# M3_Shield_Solar_V1_2.net
KiCad netlist of a schematic drawn in EAGLE
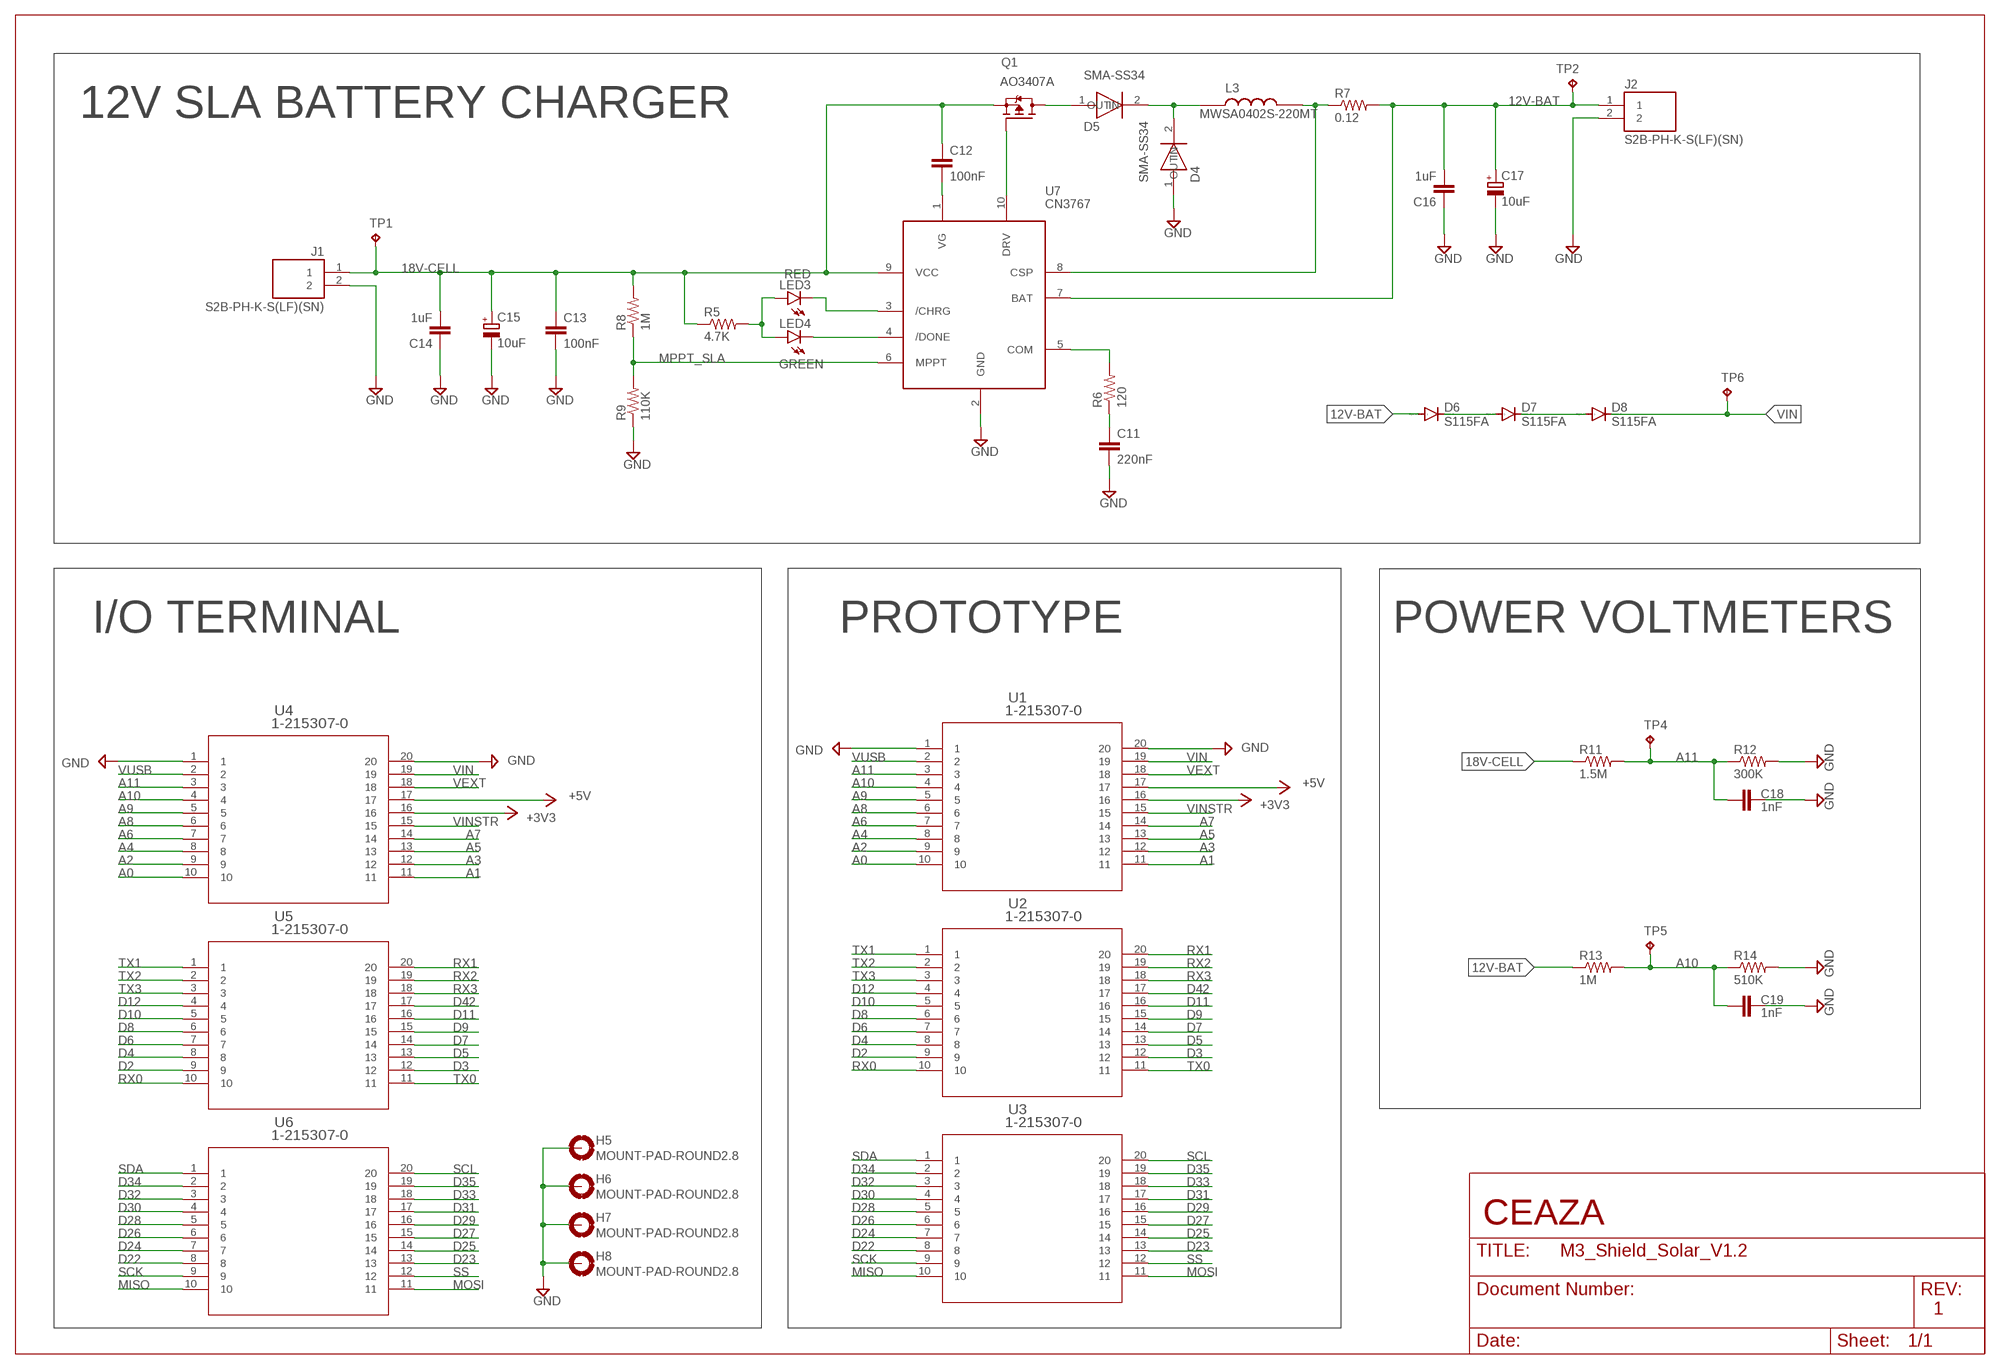
[diagram p0: schematic, sheet 1]

(export (version "E")
  (design (tool "Eeschema 10.0.6"))
  (components
    (comp (ref "C11")
      (value "220nF")
      (footprint "eagle-import:C0603K")
      (libsource (lib "eagle-import") (part "C-EUC0603K"))
    )
    (comp (ref "C12")
      (value "100nF")
      (footprint "eagle-import:C0603K")
      (libsource (lib "eagle-import") (part "C-EUC0603K"))
    )
    (comp (ref "C13")
      (value "100nF")
      (footprint "eagle-import:C0603K")
      (libsource (lib "eagle-import") (part "C-EUC0603K"))
    )
    (comp (ref "C14")
      (value "1uF")
      (footprint "eagle-import:C0603K")
      (libsource (lib "eagle-import") (part "C-EUC0603K"))
    )
    (comp (ref "C15")
      (value "10uF")
      (footprint "eagle-import:153CLV-0505")
      (libsource (lib "eagle-import") (part "CPOL-EU153CLV-0505"))
    )
    (comp (ref "C16")
      (value "1uF")
      (footprint "eagle-import:C0603K")
      (libsource (lib "eagle-import") (part "C-EUC0603K"))
    )
    (comp (ref "C17")
      (value "10uF")
      (footprint "eagle-import:153CLV-0505")
      (libsource (lib "eagle-import") (part "CPOL-EU153CLV-0505"))
    )
    (comp (ref "C18")
      (value "1nF")
      (footprint "eagle-import:C0603K")
      (libsource (lib "eagle-import") (part "C-EUC0603K"))
    )
    (comp (ref "C19")
      (value "1nF")
      (footprint "eagle-import:C0603K")
      (libsource (lib "eagle-import") (part "C-EUC0603K"))
    )
    (comp (ref "D4")
      (value "SMA-SS34")
      (footprint "eagle-import:SMA-SS34")
      (libsource (lib "eagle-import") (part "SMA-SS34"))
    )
    (comp (ref "D5")
      (value "SMA-SS34")
      (footprint "eagle-import:SMA-SS34")
      (libsource (lib "eagle-import") (part "SMA-SS34"))
    )
    (comp (ref "D6")
      (value "S115FA")
      (footprint "eagle-import:SOD-123_MINI-SMA")
      (libsource (lib "eagle-import") (part "CGRM400-G1"))
    )
    (comp (ref "D7")
      (value "S115FA")
      (footprint "eagle-import:SOD-123_MINI-SMA")
      (libsource (lib "eagle-import") (part "CGRM400-G1"))
    )
    (comp (ref "D8")
      (value "S115FA")
      (footprint "eagle-import:SOD-123_MINI-SMA")
      (libsource (lib "eagle-import") (part "CGRM400-G1"))
    )
    (comp (ref "H5")
      (value "MOUNT-PAD-ROUND2.8")
      (footprint "eagle-import:2,8-PAD")
      (libsource (lib "eagle-import") (part "MOUNT-PAD-ROUND2.8"))
    )
    (comp (ref "H6")
      (value "MOUNT-PAD-ROUND2.8")
      (footprint "eagle-import:2,8-PAD")
      (libsource (lib "eagle-import") (part "MOUNT-PAD-ROUND2.8"))
    )
    (comp (ref "H7")
      (value "MOUNT-PAD-ROUND2.8")
      (footprint "eagle-import:2,8-PAD")
      (libsource (lib "eagle-import") (part "MOUNT-PAD-ROUND2.8"))
    )
    (comp (ref "H8")
      (value "MOUNT-PAD-ROUND2.8")
      (footprint "eagle-import:2,8-PAD")
      (libsource (lib "eagle-import") (part "MOUNT-PAD-ROUND2.8"))
    )
    (comp (ref "J1")
      (value "S2B-PH-K-S(LF)(SN)")
      (footprint "eagle-import:JST_S2B-PH-K-S(LF)(SN)")
      (fields
        (field (name "DIGI-KEY_PART_NUMBER") "455-1719-ND")
        (field (name "MF") "JST Sales America Inc.")
        (field (name "MP") "S2B-PH-K-S_LF__SN_")
      )
      (libsource (lib "eagle-import") (part "S2B-PH-K-S(LF)(SN)"))
    )
    (comp (ref "J2")
      (value "S2B-PH-K-S(LF)(SN)")
      (footprint "eagle-import:JST_S2B-PH-K-S(LF)(SN)")
      (fields
        (field (name "DIGI-KEY_PART_NUMBER") "455-1719-ND")
        (field (name "MF") "JST Sales America Inc.")
        (field (name "MP") "S2B-PH-K-S_LF__SN_")
      )
      (libsource (lib "eagle-import") (part "S2B-PH-K-S(LF)(SN)"))
    )
    (comp (ref "L3")
      (value "MWSA0402S-220MT")
      (footprint "eagle-import:MWSA0402S-220MT")
      (libsource (lib "eagle-import") (part "MWSA0402S-220MT"))
    )
    (comp (ref "LED3")
      (value "RED")
      (footprint "eagle-import:CHIPLED_0603")
      (libsource (lib "eagle-import") (part "LEDCHIPLED_0603"))
    )
    (comp (ref "LED4")
      (value "GREEN")
      (footprint "eagle-import:CHIPLED_0603")
      (libsource (lib "eagle-import") (part "LEDCHIPLED_0603"))
    )
    (comp (ref "Q1")
      (value "AO3407A")
      (footprint "eagle-import:SOT95P280X125-3N")
      (fields (field (name "DIGI-KEY_PART_NUMBER") "785-1006-1-ND") (field (name "MF") "Alpha &"))
      (libsource (lib "eagle-import") (part "AO3407A"))
    )
    (comp (ref "R5")
      (value "4.7K")
      (footprint "eagle-import:R0603")
      (libsource (lib "eagle-import") (part "R-US_R0603"))
    )
    (comp (ref "R6")
      (value "120")
      (footprint "eagle-import:R0603")
      (libsource (lib "eagle-import") (part "R-US_R0603"))
    )
    (comp (ref "R7")
      (value "0.12")
      (footprint "eagle-import:R0805")
      (libsource (lib "eagle-import") (part "R-US_R0805"))
    )
    (comp (ref "R8")
      (value "1M")
      (footprint "eagle-import:R0603")
      (libsource (lib "eagle-import") (part "R-US_R0603"))
    )
    (comp (ref "R9")
      (value "110K")
      (footprint "eagle-import:R0603")
      (libsource (lib "eagle-import") (part "R-US_R0603"))
    )
    (comp (ref "R11")
      (value "1.5M")
      (footprint "eagle-import:R0603")
      (libsource (lib "eagle-import") (part "R-US_R0603"))
    )
    (comp (ref "R12")
      (value "300K")
      (footprint "eagle-import:R0603")
      (libsource (lib "eagle-import") (part "R-US_R0603"))
    )
    (comp (ref "R13")
      (value "1M")
      (footprint "eagle-import:R0603")
      (libsource (lib "eagle-import") (part "R-US_R0603"))
    )
    (comp (ref "R14")
      (value "510K")
      (footprint "eagle-import:R0603")
      (libsource (lib "eagle-import") (part "R-US_R0603"))
    )
    (comp (ref "TP1")
      (value "TPB1,27")
      (footprint "eagle-import:B1,27")
      (libsource (lib "eagle-import") (part "TPB1,27"))
    )
    (comp (ref "TP2")
      (value "TPB1,27")
      (footprint "eagle-import:B1,27")
      (libsource (lib "eagle-import") (part "TPB1,27"))
    )
    (comp (ref "TP4")
      (value "TPB1,27")
      (footprint "eagle-import:B1,27")
      (libsource (lib "eagle-import") (part "TPB1,27"))
    )
    (comp (ref "TP5")
      (value "TPB1,27")
      (footprint "eagle-import:B1,27")
      (libsource (lib "eagle-import") (part "TPB1,27"))
    )
    (comp (ref "TP6")
      (value "TPB1,27")
      (footprint "eagle-import:B1,27")
      (libsource (lib "eagle-import") (part "TPB1,27"))
    )
    (comp (ref "U1")
      (value "1-215307-0")
      (footprint "eagle-import:1-215307-0")
      (libsource (lib "eagle-import") (part "1-215307-0"))
    )
    (comp (ref "U2")
      (value "1-215307-0")
      (footprint "eagle-import:1-215307-0")
      (libsource (lib "eagle-import") (part "1-215307-0"))
    )
    (comp (ref "U3")
      (value "1-215307-0")
      (footprint "eagle-import:1-215307-0")
      (libsource (lib "eagle-import") (part "1-215307-0"))
    )
    (comp (ref "U4")
      (value "1-215307-0")
      (footprint "eagle-import:1-215307-0")
      (libsource (lib "eagle-import") (part "1-215307-0"))
    )
    (comp (ref "U5")
      (value "1-215307-0")
      (footprint "eagle-import:1-215307-0")
      (libsource (lib "eagle-import") (part "1-215307-0"))
    )
    (comp (ref "U6")
      (value "1-215307-0")
      (footprint "eagle-import:1-215307-0")
      (libsource (lib "eagle-import") (part "1-215307-0"))
    )
    (comp (ref "U7")
      (value "CN3767")
      (footprint "eagle-import:CN3767")
      (libsource (lib "eagle-import") (part "CN3767"))
    )
  )
  (nets
    (net (code "1") (name "+3V3") (class "Default")
      (node (ref "U1") (pin "16") (pinfunction "16_16") (pintype "passive"))
      (node (ref "U4") (pin "16") (pinfunction "16_16") (pintype "passive"))
    )
    (net (code "2") (name "+5V") (class "Default")
      (node (ref "U1") (pin "17") (pinfunction "17_17") (pintype "passive"))
      (node (ref "U4") (pin "17") (pinfunction "17_17") (pintype "passive"))
    )
    (net (code "3") (name "/A0") (class "Default")
      (node (ref "U1") (pin "10") (pinfunction "10_10") (pintype "passive"))
      (node (ref "U4") (pin "10") (pinfunction "10_10") (pintype "passive"))
    )
    (net (code "4") (name "/A1") (class "Default")
      (node (ref "U1") (pin "11") (pinfunction "11_11") (pintype "passive"))
      (node (ref "U4") (pin "11") (pinfunction "11_11") (pintype "passive"))
    )
    (net (code "5") (name "/A2") (class "Default")
      (node (ref "U1") (pin "9") (pinfunction "9_9") (pintype "passive"))
      (node (ref "U4") (pin "9") (pinfunction "9_9") (pintype "passive"))
    )
    (net (code "6") (name "/A3") (class "Default")
      (node (ref "U1") (pin "12") (pinfunction "12_12") (pintype "passive"))
      (node (ref "U4") (pin "12") (pinfunction "12_12") (pintype "passive"))
    )
    (net (code "7") (name "/A4") (class "Default")
      (node (ref "U1") (pin "8") (pinfunction "8_8") (pintype "passive"))
      (node (ref "U4") (pin "8") (pinfunction "8_8") (pintype "passive"))
    )
    (net (code "8") (name "/A5") (class "Default")
      (node (ref "U1") (pin "13") (pinfunction "13_13") (pintype "passive"))
      (node (ref "U4") (pin "13") (pinfunction "13_13") (pintype "passive"))
    )
    (net (code "9") (name "/A6") (class "Default")
      (node (ref "U1") (pin "7") (pinfunction "7_7") (pintype "passive"))
      (node (ref "U4") (pin "7") (pinfunction "7_7") (pintype "passive"))
    )
    (net (code "10") (name "/A7") (class "Default")
      (node (ref "U1") (pin "14") (pinfunction "14_14") (pintype "passive"))
      (node (ref "U4") (pin "14") (pinfunction "14_14") (pintype "passive"))
    )
    (net (code "11") (name "/A8") (class "Default")
      (node (ref "U1") (pin "6") (pinfunction "6_6") (pintype "passive"))
      (node (ref "U4") (pin "6") (pinfunction "6_6") (pintype "passive"))
    )
    (net (code "12") (name "/A9") (class "Default")
      (node (ref "U1") (pin "5") (pinfunction "5_5") (pintype "passive"))
      (node (ref "U4") (pin "5") (pinfunction "5_5") (pintype "passive"))
    )
    (net (code "13") (name "/A10") (class "Default")
      (node (ref "C19") (pin "1") (pinfunction "1_1") (pintype "passive"))
      (node (ref "R13") (pin "2") (pinfunction "2_2") (pintype "passive"))
      (node (ref "R14") (pin "1") (pinfunction "1_1") (pintype "passive"))
      (node (ref "TP5") (pin "TP") (pinfunction "TP_TP") (pintype "input"))
      (node (ref "U1") (pin "4") (pinfunction "4_4") (pintype "passive"))
      (node (ref "U4") (pin "4") (pinfunction "4_4") (pintype "passive"))
    )
    (net (code "14") (name "/A11") (class "Default")
      (node (ref "C18") (pin "1") (pinfunction "1_1") (pintype "passive"))
      (node (ref "R11") (pin "2") (pinfunction "2_2") (pintype "passive"))
      (node (ref "R12") (pin "1") (pinfunction "1_1") (pintype "passive"))
      (node (ref "TP4") (pin "TP") (pinfunction "TP_TP") (pintype "input"))
      (node (ref "U1") (pin "3") (pinfunction "3_3") (pintype "passive"))
      (node (ref "U4") (pin "3") (pinfunction "3_3") (pintype "passive"))
    )
    (net (code "15") (name "/D2") (class "Default")
      (node (ref "U2") (pin "9") (pinfunction "9_9") (pintype "passive"))
      (node (ref "U5") (pin "9") (pinfunction "9_9") (pintype "passive"))
    )
    (net (code "16") (name "/D3") (class "Default")
      (node (ref "U2") (pin "12") (pinfunction "12_12") (pintype "passive"))
      (node (ref "U5") (pin "12") (pinfunction "12_12") (pintype "passive"))
    )
    (net (code "17") (name "/D4") (class "Default")
      (node (ref "U2") (pin "8") (pinfunction "8_8") (pintype "passive"))
      (node (ref "U5") (pin "8") (pinfunction "8_8") (pintype "passive"))
    )
    (net (code "18") (name "/D5") (class "Default")
      (node (ref "U2") (pin "13") (pinfunction "13_13") (pintype "passive"))
      (node (ref "U5") (pin "13") (pinfunction "13_13") (pintype "passive"))
    )
    (net (code "19") (name "/D6") (class "Default")
      (node (ref "U2") (pin "7") (pinfunction "7_7") (pintype "passive"))
      (node (ref "U5") (pin "7") (pinfunction "7_7") (pintype "passive"))
    )
    (net (code "20") (name "/D7") (class "Default")
      (node (ref "U2") (pin "14") (pinfunction "14_14") (pintype "passive"))
      (node (ref "U5") (pin "14") (pinfunction "14_14") (pintype "passive"))
    )
    (net (code "21") (name "/D8") (class "Default")
      (node (ref "U2") (pin "6") (pinfunction "6_6") (pintype "passive"))
      (node (ref "U5") (pin "6") (pinfunction "6_6") (pintype "passive"))
    )
    (net (code "22") (name "/D9") (class "Default")
      (node (ref "U2") (pin "15") (pinfunction "15_15") (pintype "passive"))
      (node (ref "U5") (pin "15") (pinfunction "15_15") (pintype "passive"))
    )
    (net (code "23") (name "/D10") (class "Default")
      (node (ref "U2") (pin "5") (pinfunction "5_5") (pintype "passive"))
      (node (ref "U5") (pin "5") (pinfunction "5_5") (pintype "passive"))
    )
    (net (code "24") (name "/D11") (class "Default")
      (node (ref "U2") (pin "16") (pinfunction "16_16") (pintype "passive"))
      (node (ref "U5") (pin "16") (pinfunction "16_16") (pintype "passive"))
    )
    (net (code "25") (name "/D12") (class "Default")
      (node (ref "U2") (pin "4") (pinfunction "4_4") (pintype "passive"))
      (node (ref "U5") (pin "4") (pinfunction "4_4") (pintype "passive"))
    )
    (net (code "26") (name "/D22") (class "Default")
      (node (ref "U3") (pin "8") (pinfunction "8_8") (pintype "passive"))
      (node (ref "U6") (pin "8") (pinfunction "8_8") (pintype "passive"))
    )
    (net (code "27") (name "/D23") (class "Default")
      (node (ref "U3") (pin "13") (pinfunction "13_13") (pintype "passive"))
      (node (ref "U6") (pin "13") (pinfunction "13_13") (pintype "passive"))
    )
    (net (code "28") (name "/D24") (class "Default")
      (node (ref "U3") (pin "7") (pinfunction "7_7") (pintype "passive"))
      (node (ref "U6") (pin "7") (pinfunction "7_7") (pintype "passive"))
    )
    (net (code "29") (name "/D25") (class "Default")
      (node (ref "U3") (pin "14") (pinfunction "14_14") (pintype "passive"))
      (node (ref "U6") (pin "14") (pinfunction "14_14") (pintype "passive"))
    )
    (net (code "30") (name "/D26") (class "Default")
      (node (ref "U3") (pin "6") (pinfunction "6_6") (pintype "passive"))
      (node (ref "U6") (pin "6") (pinfunction "6_6") (pintype "passive"))
    )
    (net (code "31") (name "/D27") (class "Default")
      (node (ref "U3") (pin "15") (pinfunction "15_15") (pintype "passive"))
      (node (ref "U6") (pin "15") (pinfunction "15_15") (pintype "passive"))
    )
    (net (code "32") (name "/D28") (class "Default")
      (node (ref "U3") (pin "5") (pinfunction "5_5") (pintype "passive"))
      (node (ref "U6") (pin "5") (pinfunction "5_5") (pintype "passive"))
    )
    (net (code "33") (name "/D29") (class "Default")
      (node (ref "U3") (pin "16") (pinfunction "16_16") (pintype "passive"))
      (node (ref "U6") (pin "16") (pinfunction "16_16") (pintype "passive"))
    )
    (net (code "34") (name "/D30") (class "Default")
      (node (ref "U3") (pin "4") (pinfunction "4_4") (pintype "passive"))
      (node (ref "U6") (pin "4") (pinfunction "4_4") (pintype "passive"))
    )
    (net (code "35") (name "/D31") (class "Default")
      (node (ref "U3") (pin "17") (pinfunction "17_17") (pintype "passive"))
      (node (ref "U6") (pin "17") (pinfunction "17_17") (pintype "passive"))
    )
    (net (code "36") (name "/D32") (class "Default")
      (node (ref "U3") (pin "3") (pinfunction "3_3") (pintype "passive"))
      (node (ref "U6") (pin "3") (pinfunction "3_3") (pintype "passive"))
    )
    (net (code "37") (name "/D33") (class "Default")
      (node (ref "U3") (pin "18") (pinfunction "18_18") (pintype "passive"))
      (node (ref "U6") (pin "18") (pinfunction "18_18") (pintype "passive"))
    )
    (net (code "38") (name "/D34") (class "Default")
      (node (ref "U3") (pin "2") (pinfunction "2_2") (pintype "passive"))
      (node (ref "U6") (pin "2") (pinfunction "2_2") (pintype "passive"))
    )
    (net (code "39") (name "/D35") (class "Default")
      (node (ref "U3") (pin "19") (pinfunction "19_19") (pintype "passive"))
      (node (ref "U6") (pin "19") (pinfunction "19_19") (pintype "passive"))
    )
    (net (code "40") (name "/D42") (class "Default")
      (node (ref "U2") (pin "17") (pinfunction "17_17") (pintype "passive"))
      (node (ref "U5") (pin "17") (pinfunction "17_17") (pintype "passive"))
    )
    (net (code "41") (name "/MISO") (class "Default")
      (node (ref "U3") (pin "10") (pinfunction "10_10") (pintype "passive"))
      (node (ref "U6") (pin "10") (pinfunction "10_10") (pintype "passive"))
    )
    (net (code "42") (name "/MOSI") (class "Default")
      (node (ref "U3") (pin "11") (pinfunction "11_11") (pintype "passive"))
      (node (ref "U6") (pin "11") (pinfunction "11_11") (pintype "passive"))
    )
    (net (code "43") (name "/MPPT_SLA") (class "Default")
      (node (ref "R8") (pin "1") (pinfunction "1_1") (pintype "passive"))
      (node (ref "R9") (pin "2") (pinfunction "2_2") (pintype "passive"))
      (node (ref "U7") (pin "6") (pinfunction "MPPT_6") (pintype "bidirectional"))
    )
    (net (code "44") (name "/RX0") (class "Default")
      (node (ref "U2") (pin "10") (pinfunction "10_10") (pintype "passive"))
      (node (ref "U5") (pin "10") (pinfunction "10_10") (pintype "passive"))
    )
    (net (code "45") (name "/RX1") (class "Default")
      (node (ref "U2") (pin "20") (pinfunction "20_20") (pintype "passive"))
      (node (ref "U5") (pin "20") (pinfunction "20_20") (pintype "passive"))
    )
    (net (code "46") (name "/RX2") (class "Default")
      (node (ref "U2") (pin "19") (pinfunction "19_19") (pintype "passive"))
      (node (ref "U5") (pin "19") (pinfunction "19_19") (pintype "passive"))
    )
    (net (code "47") (name "/RX3") (class "Default")
      (node (ref "U2") (pin "18") (pinfunction "18_18") (pintype "passive"))
      (node (ref "U5") (pin "18") (pinfunction "18_18") (pintype "passive"))
    )
    (net (code "48") (name "/SCK") (class "Default")
      (node (ref "U3") (pin "9") (pinfunction "9_9") (pintype "passive"))
      (node (ref "U6") (pin "9") (pinfunction "9_9") (pintype "passive"))
    )
    (net (code "49") (name "/SCL") (class "Default")
      (node (ref "U3") (pin "20") (pinfunction "20_20") (pintype "passive"))
      (node (ref "U6") (pin "20") (pinfunction "20_20") (pintype "passive"))
    )
    (net (code "50") (name "/SDA") (class "Default")
      (node (ref "U3") (pin "1") (pinfunction "1_1") (pintype "passive"))
      (node (ref "U6") (pin "1") (pinfunction "1_1") (pintype "passive"))
    )
    (net (code "51") (name "/SS") (class "Default")
      (node (ref "U3") (pin "12") (pinfunction "12_12") (pintype "passive"))
      (node (ref "U6") (pin "12") (pinfunction "12_12") (pintype "passive"))
    )
    (net (code "52") (name "/TX0") (class "Default")
      (node (ref "U2") (pin "11") (pinfunction "11_11") (pintype "passive"))
      (node (ref "U5") (pin "11") (pinfunction "11_11") (pintype "passive"))
    )
    (net (code "53") (name "/TX1") (class "Default")
      (node (ref "U2") (pin "1") (pinfunction "1_1") (pintype "passive"))
      (node (ref "U5") (pin "1") (pinfunction "1_1") (pintype "passive"))
    )
    (net (code "54") (name "/TX2") (class "Default")
      (node (ref "U2") (pin "2") (pinfunction "2_2") (pintype "passive"))
      (node (ref "U5") (pin "2") (pinfunction "2_2") (pintype "passive"))
    )
    (net (code "55") (name "/TX3") (class "Default")
      (node (ref "U2") (pin "3") (pinfunction "3_3") (pintype "passive"))
      (node (ref "U5") (pin "3") (pinfunction "3_3") (pintype "passive"))
    )
    (net (code "56") (name "/VEXT") (class "Default")
      (node (ref "U1") (pin "18") (pinfunction "18_18") (pintype "passive"))
      (node (ref "U4") (pin "18") (pinfunction "18_18") (pintype "passive"))
    )
    (net (code "57") (name "/VINSTR") (class "Default")
      (node (ref "U1") (pin "15") (pinfunction "15_15") (pintype "passive"))
      (node (ref "U4") (pin "15") (pinfunction "15_15") (pintype "passive"))
    )
    (net (code "58") (name "/VUSB") (class "Default")
      (node (ref "U1") (pin "2") (pinfunction "2_2") (pintype "passive"))
      (node (ref "U4") (pin "2") (pinfunction "2_2") (pintype "passive"))
    )
    (net (code "59") (name "12V-BAT") (class "Default")
      (node (ref "C16") (pin "2") (pinfunction "2_2") (pintype "passive"))
      (node (ref "C17") (pin "+") (pinfunction "+_+") (pintype "passive"))
      (node (ref "D6") (pin "A") (pinfunction "A_A") (pintype "passive"))
      (node (ref "J2") (pin "1") (pinfunction "1_1") (pintype "passive"))
      (node (ref "R13") (pin "1") (pinfunction "1_1") (pintype "passive"))
      (node (ref "R7") (pin "2") (pinfunction "2_2") (pintype "passive"))
      (node (ref "TP2") (pin "TP") (pinfunction "TP_TP") (pintype "input"))
      (node (ref "U7") (pin "7") (pinfunction "BAT_7") (pintype "bidirectional"))
    )
    (net (code "60") (name "18V-CELL") (class "Default")
      (node (ref "C12") (pin "1") (pinfunction "1_1") (pintype "passive"))
      (node (ref "C13") (pin "1") (pinfunction "1_1") (pintype "passive"))
      (node (ref "C14") (pin "2") (pinfunction "2_2") (pintype "passive"))
      (node (ref "C15") (pin "+") (pinfunction "+_+") (pintype "passive"))
      (node (ref "J1") (pin "1") (pinfunction "1_1") (pintype "passive"))
      (node (ref "Q1") (pin "2") (pinfunction "S_2") (pintype "passive"))
      (node (ref "R11") (pin "1") (pinfunction "1_1") (pintype "passive"))
      (node (ref "R5") (pin "1") (pinfunction "1_1") (pintype "passive"))
      (node (ref "R8") (pin "2") (pinfunction "2_2") (pintype "passive"))
      (node (ref "TP1") (pin "TP") (pinfunction "TP_TP") (pintype "input"))
      (node (ref "U7") (pin "9") (pinfunction "VCC_9") (pintype "bidirectional"))
    )
    (net (code "61") (name "GND") (class "Default")
      (node (ref "C11") (pin "2") (pinfunction "2_2") (pintype "passive"))
      (node (ref "C13") (pin "2") (pinfunction "2_2") (pintype "passive"))
      (node (ref "C14") (pin "1") (pinfunction "1_1") (pintype "passive"))
      (node (ref "C15") (pin "-") (pinfunction "-_-") (pintype "passive"))
      (node (ref "C16") (pin "1") (pinfunction "1_1") (pintype "passive"))
      (node (ref "C17") (pin "-") (pinfunction "-_-") (pintype "passive"))
      (node (ref "C18") (pin "2") (pinfunction "2_2") (pintype "passive"))
      (node (ref "C19") (pin "2") (pinfunction "2_2") (pintype "passive"))
      (node (ref "D4") (pin "1") (pinfunction "IN_1") (pintype "input"))
      (node (ref "H5") (pin "B2,8") (pinfunction "MOUNT_B2,8") (pintype "passive"))
      (node (ref "H6") (pin "B2,8") (pinfunction "MOUNT_B2,8") (pintype "passive"))
      (node (ref "H7") (pin "B2,8") (pinfunction "MOUNT_B2,8") (pintype "passive"))
      (node (ref "H8") (pin "B2,8") (pinfunction "MOUNT_B2,8") (pintype "passive"))
      (node (ref "J1") (pin "2") (pinfunction "2_2") (pintype "passive"))
      (node (ref "J2") (pin "2") (pinfunction "2_2") (pintype "passive"))
      (node (ref "R12") (pin "2") (pinfunction "2_2") (pintype "passive"))
      (node (ref "R14") (pin "2") (pinfunction "2_2") (pintype "passive"))
      (node (ref "R9") (pin "1") (pinfunction "1_1") (pintype "passive"))
      (node (ref "U1") (pin "1") (pinfunction "1_1") (pintype "passive"))
      (node (ref "U1") (pin "20") (pinfunction "20_20") (pintype "passive"))
      (node (ref "U4") (pin "1") (pinfunction "1_1") (pintype "passive"))
      (node (ref "U4") (pin "20") (pinfunction "20_20") (pintype "passive"))
      (node (ref "U7") (pin "2") (pinfunction "GND_2") (pintype "bidirectional"))
    )
    (net (code "62") (name "Net-(C11-Pad1)") (class "Default")
      (node (ref "C11") (pin "1") (pinfunction "1_1") (pintype "passive"))
      (node (ref "R6") (pin "1") (pinfunction "1_1") (pintype "passive"))
    )
    (net (code "63") (name "Net-(D4-OUT)") (class "Default")
      (node (ref "D4") (pin "2") (pinfunction "OUT_2") (pintype "bidirectional"))
      (node (ref "D5") (pin "2") (pinfunction "OUT_2") (pintype "bidirectional"))
      (node (ref "L3") (pin "P$1") (pinfunction "P$1_P$1") (pintype "bidirectional"))
    )
    (net (code "64") (name "Net-(D5-IN)") (class "Default")
      (node (ref "D5") (pin "1") (pinfunction "IN_1") (pintype "input"))
      (node (ref "Q1") (pin "3") (pinfunction "D_3") (pintype "passive"))
    )
    (net (code "65") (name "Net-(D6-PadC)") (class "Default")
      (node (ref "D6") (pin "C") (pinfunction "C_C") (pintype "passive"))
      (node (ref "D7") (pin "A") (pinfunction "A_A") (pintype "passive"))
    )
    (net (code "66") (name "Net-(D7-PadC)") (class "Default")
      (node (ref "D7") (pin "C") (pinfunction "C_C") (pintype "passive"))
      (node (ref "D8") (pin "A") (pinfunction "A_A") (pintype "passive"))
    )
    (net (code "67") (name "Net-(LED3-PadA)") (class "Default")
      (node (ref "LED3") (pin "A") (pinfunction "A_A") (pintype "passive"))
      (node (ref "LED4") (pin "A") (pinfunction "A_A") (pintype "passive"))
      (node (ref "R5") (pin "2") (pinfunction "2_2") (pintype "passive"))
    )
    (net (code "68") (name "Net-(Q1-G)") (class "Default")
      (node (ref "Q1") (pin "1") (pinfunction "G_1") (pintype "passive"))
      (node (ref "U7") (pin "10") (pinfunction "DRV_10") (pintype "bidirectional"))
    )
    (net (code "69") (name "Net-(U7-COM)") (class "Default")
      (node (ref "R6") (pin "2") (pinfunction "2_2") (pintype "passive"))
      (node (ref "U7") (pin "5") (pinfunction "COM_5") (pintype "bidirectional"))
    )
    (net (code "70") (name "Net-(U7-CSP)") (class "Default")
      (node (ref "L3") (pin "P$2") (pinfunction "P$2_P$2") (pintype "bidirectional"))
      (node (ref "R7") (pin "1") (pinfunction "1_1") (pintype "passive"))
      (node (ref "U7") (pin "8") (pinfunction "CSP_8") (pintype "bidirectional"))
    )
    (net (code "71") (name "Net-(U7-VG)") (class "Default")
      (node (ref "C12") (pin "2") (pinfunction "2_2") (pintype "passive"))
      (node (ref "U7") (pin "1") (pinfunction "VG_1") (pintype "bidirectional"))
    )
    (net (code "72") (name "Net-(U7-{slash}CHRG)") (class "Default")
      (node (ref "LED3") (pin "C") (pinfunction "C_C") (pintype "passive"))
      (node (ref "U7") (pin "3") (pinfunction "/CHRG_3") (pintype "bidirectional"))
    )
    (net (code "73") (name "Net-(U7-{slash}DONE)") (class "Default")
      (node (ref "LED4") (pin "C") (pinfunction "C_C") (pintype "passive"))
      (node (ref "U7") (pin "4") (pinfunction "/DONE_4") (pintype "bidirectional"))
    )
    (net (code "74") (name "VIN") (class "Default")
      (node (ref "D8") (pin "C") (pinfunction "C_C") (pintype "passive"))
      (node (ref "TP6") (pin "TP") (pinfunction "TP_TP") (pintype "input"))
      (node (ref "U1") (pin "19") (pinfunction "19_19") (pintype "passive"))
      (node (ref "U4") (pin "19") (pinfunction "19_19") (pintype "passive"))
    )
  )
)
